# EA.net
KiCad netlist of a schematic drawn in Altium Designer
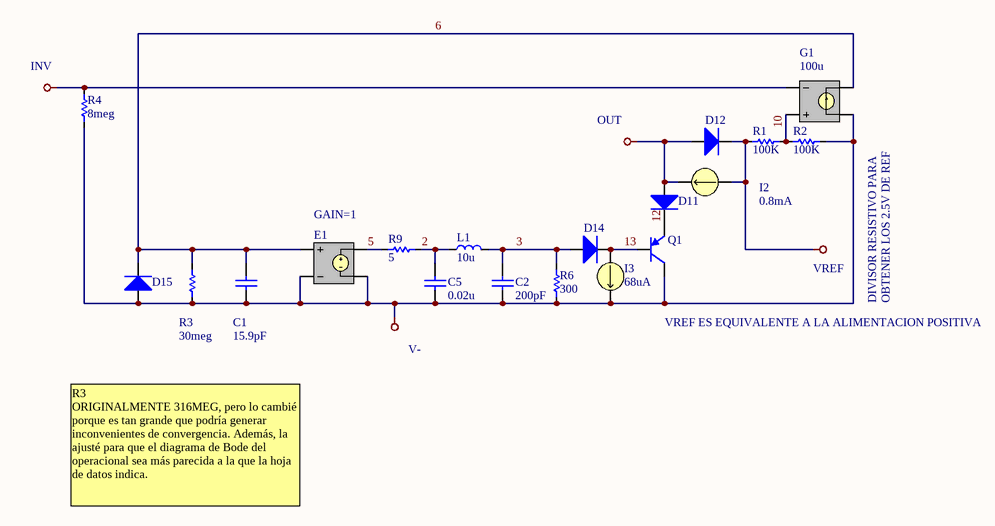
[diagram p0: EA.SCHDOC]

(export (version "E")
  (design (tool "Eeschema 10.0.6"))
  (components
    (comp (ref "C1")
      (value "15.9pF")
      (footprint "0805")
      (description "Capacitor")
      (fields (field (name "VOLTAGE") "50V") (field (name "Comment") "Cap"))
      (libsource (lib "FEDE") (part "Cap"))
    )
    (comp (ref "C2")
      (value "200pF")
      (footprint "0805")
      (description "Capacitor")
      (fields (field (name "VOLTAGE") "50V") (field (name "Comment") "Cap"))
      (libsource (lib "FEDE") (part "Cap"))
    )
    (comp (ref "C5")
      (value "0.02u")
      (footprint "0805")
      (description "Capacitor")
      (fields (field (name "VOLTAGE") "50V") (field (name "Comment") "Cap"))
      (libsource (lib "FEDE") (part "Cap"))
    )
    (comp (ref "D11")
      (value "Diode")
      (footprint "diode400")
      (description "Diodo")
      (libsource (lib "FEDE") (part "Diode"))
    )
    (comp (ref "D12")
      (value "Diode")
      (footprint "diode400")
      (description "Diodo")
      (libsource (lib "FEDE") (part "Diode"))
    )
    (comp (ref "D14")
      (value "Diode")
      (footprint "diode400")
      (description "Diodo")
      (libsource (lib "FEDE") (part "Diode"))
    )
    (comp (ref "D15")
      (value "Diode")
      (footprint "diode400")
      (description "Diodo")
      (libsource (lib "FEDE") (part "Diode"))
    )
    (comp (ref "E1")
      (value "ESRC")
      (description "Voltage Controlled Voltage Source")
      (fields (field (name "PUBLISHER") "Altium Limited"))
      (libsource (lib "Simulation Sources") (part "ESRC"))
    )
    (comp (ref "G1")
      (value "GSRC")
      (description "Voltage Controlled Current Source")
      (fields (field (name "GAIN") "100u") (field (name "PUBLISHER") "Altium Limited"))
      (libsource (lib "Simulation Sources") (part "GSRC"))
    )
    (comp (ref "I2")
      (value "0.8mA")
      (description "Current Source")
      (fields (field (name "Comment") "ISRC") (field (name "PUBLISHER") "Altium Limited"))
      (libsource (lib "Simulation Sources") (part "ISRC"))
    )
    (comp (ref "I3")
      (value "68uA")
      (description "Current Source")
      (fields (field (name "Comment") "ISRC") (field (name "PUBLISHER") "Altium Limited"))
      (libsource (lib "Simulation Sources") (part "ISRC"))
    )
    (comp (ref "L1")
      (value "10u")
      (footprint "TOROIDE TN14-9-5")
      (description "Inductor")
      (fields (field (name "Comment") "Inductor2"))
      (libsource (lib "FEDE") (part "Inductor2"))
    )
    (comp (ref "Q1")
      (value "PNP")
      (footprint "SOT23")
      (description "PNP Bipolar Transistor")
      (libsource (lib "FEDE") (part "PNP"))
    )
    (comp (ref "R1")
      (value "100K")
      (footprint "0805")
      (description "Resistor")
      (fields (field (name "POWER") "0.25W") (field (name "Comment") "Res"))
      (libsource (lib "FEDE") (part "Res"))
    )
    (comp (ref "R2")
      (value "100K")
      (footprint "0805")
      (description "Resistor")
      (fields (field (name "POWER") "0.25W") (field (name "Comment") "Res"))
      (libsource (lib "FEDE") (part "Res"))
    )
    (comp (ref "R3")
      (value "30meg")
      (footprint "0805")
      (description "Resistor")
      (fields (field (name "POWER") "0.25W") (field (name "Comment") "Res"))
      (libsource (lib "FEDE") (part "Res"))
    )
    (comp (ref "R4")
      (value "8meg")
      (footprint "0805")
      (description "Resistor")
      (fields (field (name "POWER") "0.25W") (field (name "Comment") "Res"))
      (libsource (lib "FEDE") (part "Res"))
    )
    (comp (ref "R6")
      (value "300")
      (footprint "0805")
      (description "Resistor")
      (fields (field (name "POWER") "0.25W") (field (name "Comment") "Res"))
      (libsource (lib "FEDE") (part "Res"))
    )
    (comp (ref "R9")
      (value "5")
      (footprint "0805")
      (description "Resistor")
      (fields (field (name "POWER") "0.25W") (field (name "Comment") "Res"))
      (libsource (lib "FEDE") (part "Res"))
    )
  )
  (nets
    (net (code "1") (name "/2") (class "Default")
      (node (ref "C5") (pin "2") (pinfunction "2_2") (pintype "passive"))
      (node (ref "L1") (pin "1") (pinfunction "1_1") (pintype "passive"))
      (node (ref "R9") (pin "1") (pinfunction "1_1") (pintype "passive"))
    )
    (net (code "2") (name "/3") (class "Default")
      (node (ref "C2") (pin "2") (pinfunction "2_2") (pintype "passive"))
      (node (ref "D14") (pin "1") (pinfunction "1_1") (pintype "passive"))
      (node (ref "L1") (pin "2") (pinfunction "2_2") (pintype "passive"))
      (node (ref "R6") (pin "2") (pinfunction "2_2") (pintype "passive"))
    )
    (net (code "3") (name "/5") (class "Default")
      (node (ref "E1") (pin "3") (pinfunction "N+_3") (pintype "passive"))
      (node (ref "R9") (pin "2") (pinfunction "2_2") (pintype "passive"))
    )
    (net (code "4") (name "/6") (class "Default")
      (node (ref "C1") (pin "2") (pinfunction "2_2") (pintype "passive"))
      (node (ref "D15") (pin "2") (pinfunction "2_2") (pintype "passive"))
      (node (ref "E1") (pin "1") (pinfunction "NC+_1") (pintype "passive"))
      (node (ref "G1") (pin "4") (pinfunction "N-_4") (pintype "passive"))
      (node (ref "R3") (pin "2") (pinfunction "2_2") (pintype "passive"))
    )
    (net (code "5") (name "/10") (class "Default")
      (node (ref "G1") (pin "1") (pinfunction "NC+_1") (pintype "passive"))
      (node (ref "R1") (pin "1") (pinfunction "1_1") (pintype "passive"))
      (node (ref "R2") (pin "1") (pinfunction "1_1") (pintype "passive"))
    )
    (net (code "6") (name "/12") (class "Default")
      (node (ref "D11") (pin "2") (pinfunction "2_2") (pintype "passive"))
      (node (ref "Q1") (pin "3") (pinfunction "E_3") (pintype "passive"))
    )
    (net (code "7") (name "/13") (class "Default")
      (node (ref "D14") (pin "2") (pinfunction "2_2") (pintype "passive"))
      (node (ref "I3") (pin "1") (pinfunction "1_1") (pintype "passive"))
      (node (ref "Q1") (pin "2") (pinfunction "B_2") (pintype "passive"))
    )
    (net (code "8") (name "1") (class "Default")
      (node (ref "G1") (pin "2") (pinfunction "NC-_2") (pintype "passive"))
      (node (ref "R4") (pin "2") (pinfunction "2_2") (pintype "passive"))
    )
    (net (code "9") (name "4") (class "Default")
      (node (ref "D12") (pin "2") (pinfunction "2_2") (pintype "passive"))
      (node (ref "I2") (pin "1") (pinfunction "1_1") (pintype "passive"))
      (node (ref "R1") (pin "2") (pinfunction "2_2") (pintype "passive"))
    )
    (net (code "10") (name "9") (class "Default")
      (node (ref "D11") (pin "1") (pinfunction "1_1") (pintype "passive"))
      (node (ref "D12") (pin "1") (pinfunction "1_1") (pintype "passive"))
      (node (ref "I2") (pin "2") (pinfunction "2_2") (pintype "passive"))
    )
    (net (code "11") (name "20") (class "Default")
      (node (ref "C1") (pin "1") (pinfunction "1_1") (pintype "passive"))
      (node (ref "C2") (pin "1") (pinfunction "1_1") (pintype "passive"))
      (node (ref "C5") (pin "1") (pinfunction "1_1") (pintype "passive"))
      (node (ref "D15") (pin "1") (pinfunction "1_1") (pintype "passive"))
      (node (ref "E1") (pin "2") (pinfunction "NC-_2") (pintype "passive"))
      (node (ref "E1") (pin "4") (pinfunction "N-_4") (pintype "passive"))
      (node (ref "G1") (pin "3") (pinfunction "N+_3") (pintype "passive"))
      (node (ref "I3") (pin "2") (pinfunction "2_2") (pintype "passive"))
      (node (ref "Q1") (pin "1") (pinfunction "C_1") (pintype "passive"))
      (node (ref "R2") (pin "2") (pinfunction "2_2") (pintype "passive"))
      (node (ref "R3") (pin "1") (pinfunction "1_1") (pintype "passive"))
      (node (ref "R4") (pin "1") (pinfunction "1_1") (pintype "passive"))
      (node (ref "R6") (pin "1") (pinfunction "1_1") (pintype "passive"))
    )
  )
)
